# SmartSocket_Eth.net
KiCad netlist of a schematic drawn in EAGLE
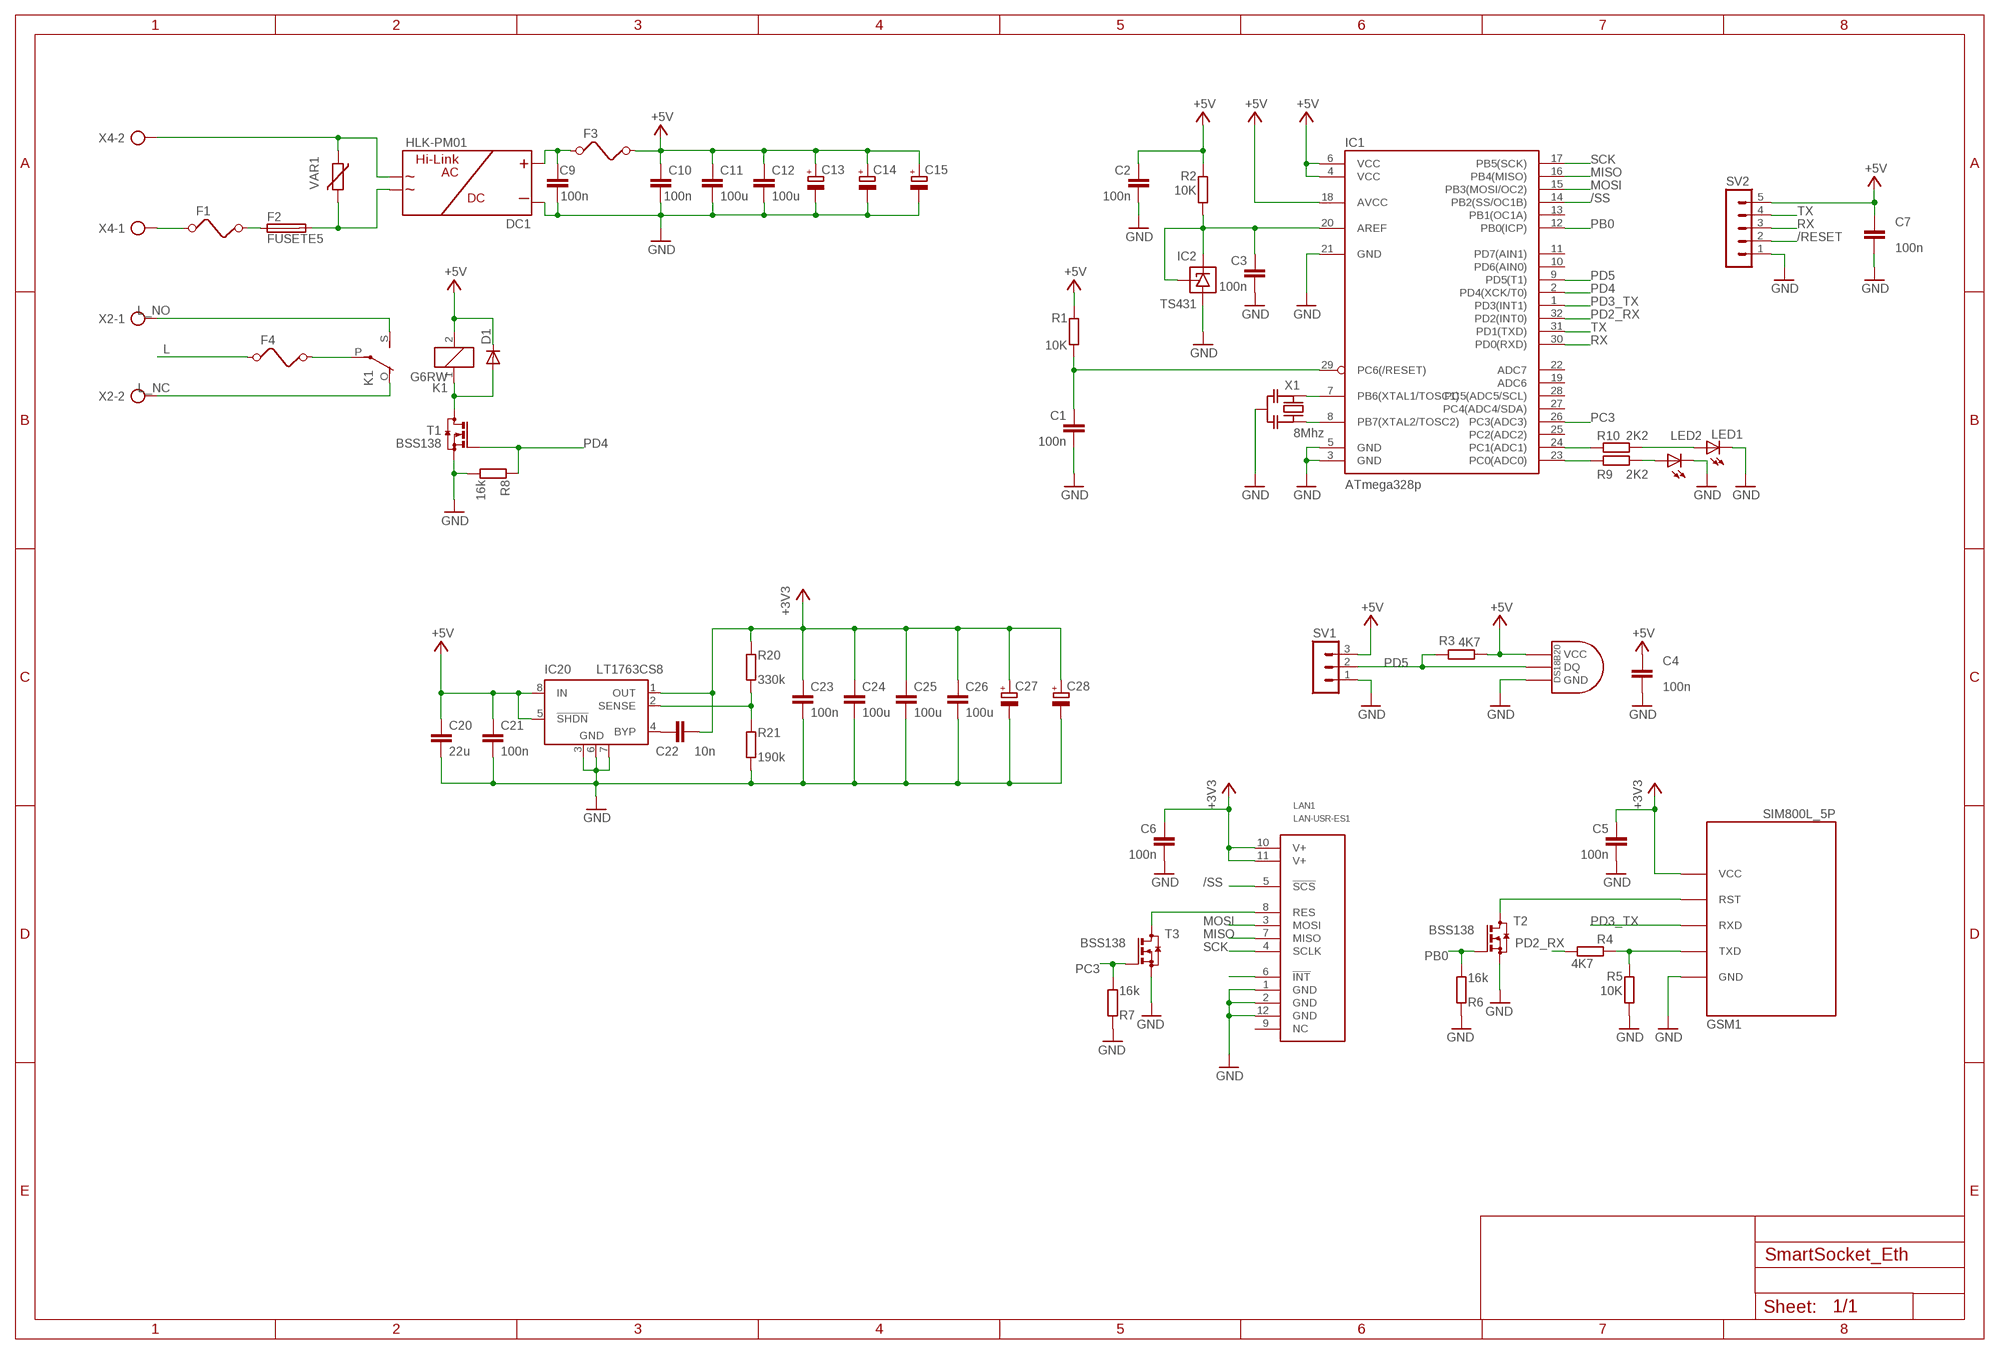
[diagram p0: schematic, sheet 1]

(export (version "E")
  (design (tool "Eeschema 10.0.6"))
  (components
    (comp (ref "18B20")
      (value "DS1820TO92")
      (footprint "eagle-import:DS1820")
      (libsource (lib "eagle-import") (part "DS1820TO92"))
    )
    (comp (ref "C1")
      (value "100n")
      (footprint "eagle-import:C0805")
      (libsource (lib "eagle-import") (part "C-EUC0805"))
    )
    (comp (ref "C2")
      (value "100n")
      (footprint "eagle-import:C0805")
      (libsource (lib "eagle-import") (part "C-EUC0805"))
    )
    (comp (ref "C3")
      (value "100n")
      (footprint "eagle-import:C0805")
      (libsource (lib "eagle-import") (part "C-EUC0805"))
    )
    (comp (ref "C4")
      (value "100n")
      (footprint "eagle-import:C0805")
      (libsource (lib "eagle-import") (part "C-EUC0805"))
    )
    (comp (ref "C5")
      (value "100n")
      (footprint "eagle-import:C0805")
      (libsource (lib "eagle-import") (part "C-EUC0805"))
    )
    (comp (ref "C6")
      (value "100n")
      (footprint "eagle-import:C0805")
      (libsource (lib "eagle-import") (part "C-EUC0805"))
    )
    (comp (ref "C7")
      (value "100n")
      (footprint "eagle-import:C0805")
      (libsource (lib "eagle-import") (part "C-EUC0805"))
    )
    (comp (ref "C9")
      (value "100n")
      (footprint "eagle-import:C0805")
      (libsource (lib "eagle-import") (part "C-EUC0805"))
    )
    (comp (ref "C10")
      (value "100n")
      (footprint "eagle-import:C0805")
      (libsource (lib "eagle-import") (part "C-EUC0805"))
    )
    (comp (ref "C11")
      (value "100u")
      (footprint "eagle-import:C1206")
      (libsource (lib "eagle-import") (part "C-EUC1206"))
    )
    (comp (ref "C12")
      (value "100u")
      (footprint "eagle-import:C1206")
      (libsource (lib "eagle-import") (part "C-EUC1206"))
    )
    (comp (ref "C13")
      (value "CPOL-EUE5-6")
      (footprint "eagle-import:E5-6")
      (libsource (lib "eagle-import") (part "CPOL-EUE5-6"))
    )
    (comp (ref "C14")
      (value "CPOL-EUSMCD")
      (footprint "eagle-import:SMC_D")
      (libsource (lib "eagle-import") (part "CPOL-EUSMCD"))
    )
    (comp (ref "C15")
      (value "CPOL-EUSMCD")
      (footprint "eagle-import:SMC_D")
      (libsource (lib "eagle-import") (part "CPOL-EUSMCD"))
    )
    (comp (ref "C20")
      (value "22u")
      (footprint "eagle-import:C0805")
      (libsource (lib "eagle-import") (part "C-EUC0805"))
    )
    (comp (ref "C21")
      (value "100n")
      (footprint "eagle-import:C0805")
      (libsource (lib "eagle-import") (part "C-EUC0805"))
    )
    (comp (ref "C22")
      (value "10n")
      (footprint "eagle-import:C0805")
      (libsource (lib "eagle-import") (part "C-EUC0805"))
    )
    (comp (ref "C23")
      (value "100n")
      (footprint "eagle-import:C1206")
      (libsource (lib "eagle-import") (part "C-EUC1206"))
    )
    (comp (ref "C24")
      (value "100u")
      (footprint "eagle-import:C1206")
      (libsource (lib "eagle-import") (part "C-EUC1206"))
    )
    (comp (ref "C25")
      (value "100u")
      (footprint "eagle-import:C1206")
      (libsource (lib "eagle-import") (part "C-EUC1206"))
    )
    (comp (ref "C26")
      (value "100u")
      (footprint "eagle-import:C1206")
      (libsource (lib "eagle-import") (part "C-EUC1206"))
    )
    (comp (ref "C27")
      (value "CPOL-EUE5-4")
      (footprint "eagle-import:E5-4")
      (libsource (lib "eagle-import") (part "CPOL-EUE5-4"))
    )
    (comp (ref "C28")
      (value "CPOL-EUSMCD")
      (footprint "eagle-import:SMC_D")
      (libsource (lib "eagle-import") (part "CPOL-EUSMCD"))
    )
    (comp (ref "D1")
      (value "DIODE-MELF-MLL41")
      (footprint "eagle-import:MELF-MLL41")
      (libsource (lib "eagle-import") (part "DIODE-MELF-MLL41"))
    )
    (comp (ref "DC1")
      (value "HLK-PM01")
      (footprint "eagle-import:HLK-3W")
      (libsource (lib "eagle-import") (part "HLK-PM01"))
    )
    (comp (ref "F1")
      (value "FUSE")
      (footprint "eagle-import:FUSE")
      (libsource (lib "eagle-import") (part "FUSE"))
    )
    (comp (ref "F2")
      (value "FUSETE5")
      (footprint "eagle-import:TE5")
      (libsource (lib "eagle-import") (part "FUSETE5"))
    )
    (comp (ref "F3")
      (value "FUSE")
      (footprint "eagle-import:FUSE")
      (libsource (lib "eagle-import") (part "FUSE"))
    )
    (comp (ref "F4")
      (value "FUSE")
      (footprint "eagle-import:FUSE")
      (libsource (lib "eagle-import") (part "FUSE"))
    )
    (comp (ref "GSM1")
      (value "SIM800L_5P")
      (footprint "eagle-import:SIM800L_5P")
      (libsource (lib "eagle-import") (part "SIM800L_5P"))
    )
    (comp (ref "IC1")
      (value "ATmega328p")
      (footprint "eagle-import:TQFP32-08")
      (fields (field (name "MPN") "ATMEGA8-16AU"))
      (libsource (lib "eagle-import") (part "MEGA8-AI"))
    )
    (comp (ref "IC2")
      (value "TS431")
      (footprint "eagle-import:SOT23")
      (libsource (lib "eagle-import") (part "TS431CX"))
    )
    (comp (ref "IC20")
      (value "LT1763CS8")
      (footprint "eagle-import:SOIC8")
      (fields (field (name "MPN") "LT1763CS8-2.5"))
      (libsource (lib "eagle-import") (part "LT1763CS8-2.5"))
    )
    (comp (ref "K1")
      (value "G6RW")
      (footprint "eagle-import:G6RW")
      (libsource (lib "eagle-import") (part "G6RW"))
    )
    (comp (ref "LAN1")
      (value "LAN-USR-ES1")
      (footprint "eagle-import:USR-ES1")
      (libsource (lib "eagle-import") (part "LAN-USR-ES1"))
    )
    (comp (ref "LED1")
      (value "LED3MM")
      (footprint "eagle-import:LED3MM")
      (libsource (lib "eagle-import") (part "LED3MM"))
    )
    (comp (ref "LED2")
      (value "LED3MM")
      (footprint "eagle-import:LED3MM")
      (libsource (lib "eagle-import") (part "LED3MM"))
    )
    (comp (ref "R1")
      (value "10K")
      (footprint "eagle-import:M0805")
      (libsource (lib "eagle-import") (part "R-EU_M0805"))
    )
    (comp (ref "R2")
      (value "10K")
      (footprint "eagle-import:M0805")
      (libsource (lib "eagle-import") (part "R-EU_M0805"))
    )
    (comp (ref "R3")
      (value "4K7")
      (footprint "eagle-import:M0805")
      (libsource (lib "eagle-import") (part "R-EU_M0805"))
    )
    (comp (ref "R4")
      (value "4K7")
      (footprint "eagle-import:M0805")
      (libsource (lib "eagle-import") (part "R-EU_M0805"))
    )
    (comp (ref "R5")
      (value "10K")
      (footprint "eagle-import:M0805")
      (libsource (lib "eagle-import") (part "R-EU_M0805"))
    )
    (comp (ref "R6")
      (value "16k")
      (footprint "eagle-import:M0805")
      (libsource (lib "eagle-import") (part "R-EU_M0805"))
    )
    (comp (ref "R7")
      (value "16k")
      (footprint "eagle-import:M0805")
      (libsource (lib "eagle-import") (part "R-EU_M0805"))
    )
    (comp (ref "R8")
      (value "16k")
      (footprint "eagle-import:M0805")
      (libsource (lib "eagle-import") (part "R-EU_M0805"))
    )
    (comp (ref "R9")
      (value "2K2")
      (footprint "eagle-import:M0805")
      (libsource (lib "eagle-import") (part "R-EU_M0805"))
    )
    (comp (ref "R10")
      (value "2K2")
      (footprint "eagle-import:M0805")
      (libsource (lib "eagle-import") (part "R-EU_M0805"))
    )
    (comp (ref "R20")
      (value "330k")
      (footprint "eagle-import:M0805")
      (libsource (lib "eagle-import") (part "R-EU_M0805"))
    )
    (comp (ref "R21")
      (value "190k")
      (footprint "eagle-import:M0805")
      (libsource (lib "eagle-import") (part "R-EU_M0805"))
    )
    (comp (ref "SV1")
      (value "MA03-1")
      (footprint "eagle-import:MA03-1")
      (libsource (lib "eagle-import") (part "MA03-1"))
    )
    (comp (ref "SV2")
      (value "MA05-1")
      (footprint "eagle-import:MA05-1")
      (libsource (lib "eagle-import") (part "MA05-1"))
    )
    (comp (ref "T1")
      (value "BSS138")
      (footprint "eagle-import:SOT23")
      (libsource (lib "eagle-import") (part "BSS123"))
    )
    (comp (ref "T2")
      (value "BSS138")
      (footprint "eagle-import:SOT23")
      (libsource (lib "eagle-import") (part "BSS123"))
    )
    (comp (ref "T3")
      (value "BSS138")
      (footprint "eagle-import:SOT23")
      (libsource (lib "eagle-import") (part "BSS123"))
    )
    (comp (ref "VAR1")
      (value "VARISTORS07K40")
      (footprint "eagle-import:S07K40")
      (libsource (lib "eagle-import") (part "VARISTORS07K40"))
    )
    (comp (ref "X1")
      (value "8Mhz")
      (footprint "eagle-import:CERALOCK_CSTCE_G")
      (libsource (lib "eagle-import") (part "CERMOSC-?CERALOCK-CSTCE_G"))
    )
    (comp (ref "X2")
      (value "AK500/2")
      (footprint "eagle-import:AK500_2")
      (libsource (lib "eagle-import") (part "AK500/2"))
    )
    (comp (ref "X4")
      (value "AK500/2")
      (footprint "eagle-import:AK500_2")
      (libsource (lib "eagle-import") (part "AK500/2"))
    )
  )
  (nets
    (net (code "1") (name "+3V3") (class "Default")
      (node (ref "C22") (pin "1") (pinfunction "1_1") (pintype "passive"))
      (node (ref "C23") (pin "1") (pinfunction "1_1") (pintype "passive"))
      (node (ref "C24") (pin "1") (pinfunction "1_1") (pintype "passive"))
      (node (ref "C25") (pin "1") (pinfunction "1_1") (pintype "passive"))
      (node (ref "C26") (pin "1") (pinfunction "1_1") (pintype "passive"))
      (node (ref "C27") (pin "+") (pinfunction "+_+") (pintype "passive"))
      (node (ref "C28") (pin "+") (pinfunction "+_+") (pintype "passive"))
      (node (ref "C5") (pin "2") (pinfunction "2_2") (pintype "passive"))
      (node (ref "C6") (pin "2") (pinfunction "2_2") (pintype "passive"))
      (node (ref "GSM1") (pin "P$1") (pinfunction "VCC_P$1") (pintype "bidirectional"))
      (node (ref "IC20") (pin "1") (pinfunction "OUT_1") (pintype "passive"))
      (node (ref "LAN1") (pin "10") (pinfunction "V+_10") (pintype "power_in"))
      (node (ref "LAN1") (pin "11") (pinfunction "V+_11") (pintype "power_in"))
      (node (ref "R20") (pin "2") (pinfunction "2_2") (pintype "passive"))
    )
    (net (code "2") (name "+5V") (class "Default")
      (node (ref "18B20") (pin "VDD") (pinfunction "VCC_VDD") (pintype "power_in"))
      (node (ref "C10") (pin "2") (pinfunction "2_2") (pintype "passive"))
      (node (ref "C11") (pin "1") (pinfunction "1_1") (pintype "passive"))
      (node (ref "C12") (pin "1") (pinfunction "1_1") (pintype "passive"))
      (node (ref "C13") (pin "+") (pinfunction "+_+") (pintype "passive"))
      (node (ref "C14") (pin "+") (pinfunction "+_+") (pintype "passive"))
      (node (ref "C15") (pin "+") (pinfunction "+_+") (pintype "passive"))
      (node (ref "C2") (pin "2") (pinfunction "2_2") (pintype "passive"))
      (node (ref "C20") (pin "1") (pinfunction "1_1") (pintype "passive"))
      (node (ref "C21") (pin "1") (pinfunction "1_1") (pintype "passive"))
      (node (ref "C4") (pin "2") (pinfunction "2_2") (pintype "passive"))
      (node (ref "C7") (pin "2") (pinfunction "2_2") (pintype "passive"))
      (node (ref "D1") (pin "C") (pinfunction "C_C") (pintype "passive"))
      (node (ref "F3") (pin "2") (pinfunction "2_2") (pintype "passive"))
      (node (ref "IC1") (pin "18") (pinfunction "AVCC_18") (pintype "power_in"))
      (node (ref "IC1") (pin "4") (pinfunction "VCC_4") (pintype "power_in"))
      (node (ref "IC1") (pin "6") (pinfunction "VCC_6") (pintype "power_in"))
      (node (ref "IC20") (pin "5") (pinfunction "~{SHDN}_5") (pintype "input"))
      (node (ref "IC20") (pin "8") (pinfunction "IN_8") (pintype "input"))
      (node (ref "K1") (pin "2") (pinfunction "2_2") (pintype "passive"))
      (node (ref "R1") (pin "2") (pinfunction "2_2") (pintype "passive"))
      (node (ref "R2") (pin "2") (pinfunction "2_2") (pintype "passive"))
      (node (ref "R3") (pin "2") (pinfunction "2_2") (pintype "passive"))
      (node (ref "SV1") (pin "3") (pinfunction "3_3") (pintype "passive"))
      (node (ref "SV2") (pin "5") (pinfunction "5_5") (pintype "passive"))
    )
    (net (code "3") (name "/L") (class "Default")
      (node (ref "F1") (pin "1") (pinfunction "1_1") (pintype "passive"))
      (node (ref "F4") (pin "1") (pinfunction "1_1") (pintype "passive"))
      (node (ref "X4") (pin "1") (pinfunction "KL_1") (pintype "passive"))
    )
    (net (code "4") (name "/L_NC") (class "Default")
      (node (ref "K1") (pin "O") (pinfunction "O_O") (pintype "passive"))
      (node (ref "X2") (pin "2") (pinfunction "KL_2") (pintype "passive"))
    )
    (net (code "5") (name "/L_NO") (class "Default")
      (node (ref "K1") (pin "S") (pinfunction "S_S") (pintype "passive"))
      (node (ref "X2") (pin "1") (pinfunction "KL_1") (pintype "passive"))
    )
    (net (code "6") (name "/MISO") (class "Default")
      (node (ref "IC1") (pin "16") (pinfunction "PB4(MISO)_16") (pintype "bidirectional"))
      (node (ref "LAN1") (pin "7") (pinfunction "MISO_7") (pintype "bidirectional"))
    )
    (net (code "7") (name "/MOSI") (class "Default")
      (node (ref "IC1") (pin "15") (pinfunction "PB3(MOSI/OC2)_15") (pintype "bidirectional"))
      (node (ref "LAN1") (pin "3") (pinfunction "MOSI_3") (pintype "bidirectional"))
    )
    (net (code "8") (name "/PB0") (class "Default")
      (node (ref "IC1") (pin "12") (pinfunction "PB0(ICP)_12") (pintype "bidirectional"))
      (node (ref "R6") (pin "2") (pinfunction "2_2") (pintype "passive"))
      (node (ref "T2") (pin "1") (pinfunction "G_1") (pintype "passive"))
    )
    (net (code "9") (name "/PC3") (class "Default")
      (node (ref "IC1") (pin "26") (pinfunction "PC3(ADC3)_26") (pintype "bidirectional"))
      (node (ref "R7") (pin "2") (pinfunction "2_2") (pintype "passive"))
      (node (ref "T3") (pin "1") (pinfunction "G_1") (pintype "passive"))
    )
    (net (code "10") (name "/PD2_RX") (class "Default")
      (node (ref "IC1") (pin "32") (pinfunction "PD2(INT0)_32") (pintype "bidirectional"))
      (node (ref "R4") (pin "2") (pinfunction "2_2") (pintype "passive"))
    )
    (net (code "11") (name "/PD3_TX") (class "Default")
      (node (ref "GSM1") (pin "P$3") (pinfunction "RXD_P$3") (pintype "bidirectional"))
      (node (ref "IC1") (pin "1") (pinfunction "PD3(INT1)_1") (pintype "bidirectional"))
    )
    (net (code "12") (name "/PD4") (class "Default")
      (node (ref "IC1") (pin "2") (pinfunction "PD4(XCK/T0)_2") (pintype "bidirectional"))
      (node (ref "R8") (pin "1") (pinfunction "1_1") (pintype "passive"))
      (node (ref "T1") (pin "1") (pinfunction "G_1") (pintype "passive"))
    )
    (net (code "13") (name "/PD5") (class "Default")
      (node (ref "18B20") (pin "DQ") (pinfunction "DQ_DQ") (pintype "bidirectional"))
      (node (ref "IC1") (pin "9") (pinfunction "PD5(T1)_9") (pintype "bidirectional"))
      (node (ref "R3") (pin "1") (pinfunction "1_1") (pintype "passive"))
      (node (ref "SV1") (pin "2") (pinfunction "2_2") (pintype "passive"))
    )
    (net (code "14") (name "/RX") (class "Default")
      (node (ref "IC1") (pin "30") (pinfunction "PD0(RXD)_30") (pintype "bidirectional"))
      (node (ref "SV2") (pin "3") (pinfunction "3_3") (pintype "passive"))
    )
    (net (code "15") (name "/SCK") (class "Default")
      (node (ref "IC1") (pin "17") (pinfunction "PB5(SCK)_17") (pintype "bidirectional"))
      (node (ref "LAN1") (pin "4") (pinfunction "SCLK_4") (pintype "input"))
    )
    (net (code "16") (name "/TX") (class "Default")
      (node (ref "IC1") (pin "31") (pinfunction "PD1(TXD)_31") (pintype "bidirectional"))
      (node (ref "SV2") (pin "4") (pinfunction "4_4") (pintype "passive"))
    )
    (net (code "17") (name "/{slash}RESET") (class "Default")
      (node (ref "C1") (pin "2") (pinfunction "2_2") (pintype "passive"))
      (node (ref "IC1") (pin "29") (pinfunction "PC6(/RESET)_29") (pintype "bidirectional"))
      (node (ref "R1") (pin "1") (pinfunction "1_1") (pintype "passive"))
      (node (ref "SV2") (pin "2") (pinfunction "2_2") (pintype "passive"))
    )
    (net (code "18") (name "/{slash}SS") (class "Default")
      (node (ref "IC1") (pin "14") (pinfunction "PB2(SS/OC1B)_14") (pintype "bidirectional"))
      (node (ref "LAN1") (pin "5") (pinfunction "~{SCS}_5") (pintype "input"))
    )
    (net (code "19") (name "GND") (class "Default")
      (node (ref "18B20") (pin "GND") (pinfunction "GND_GND") (pintype "power_in"))
      (node (ref "C1") (pin "1") (pinfunction "1_1") (pintype "passive"))
      (node (ref "C10") (pin "1") (pinfunction "1_1") (pintype "passive"))
      (node (ref "C11") (pin "2") (pinfunction "2_2") (pintype "passive"))
      (node (ref "C12") (pin "2") (pinfunction "2_2") (pintype "passive"))
      (node (ref "C13") (pin "-") (pinfunction "-_-") (pintype "passive"))
      (node (ref "C14") (pin "-") (pinfunction "-_-") (pintype "passive"))
      (node (ref "C15") (pin "-") (pinfunction "-_-") (pintype "passive"))
      (node (ref "C2") (pin "1") (pinfunction "1_1") (pintype "passive"))
      (node (ref "C20") (pin "2") (pinfunction "2_2") (pintype "passive"))
      (node (ref "C21") (pin "2") (pinfunction "2_2") (pintype "passive"))
      (node (ref "C23") (pin "2") (pinfunction "2_2") (pintype "passive"))
      (node (ref "C24") (pin "2") (pinfunction "2_2") (pintype "passive"))
      (node (ref "C25") (pin "2") (pinfunction "2_2") (pintype "passive"))
      (node (ref "C26") (pin "2") (pinfunction "2_2") (pintype "passive"))
      (node (ref "C27") (pin "-") (pinfunction "-_-") (pintype "passive"))
      (node (ref "C28") (pin "-") (pinfunction "-_-") (pintype "passive"))
      (node (ref "C3") (pin "1") (pinfunction "1_1") (pintype "passive"))
      (node (ref "C4") (pin "1") (pinfunction "1_1") (pintype "passive"))
      (node (ref "C5") (pin "1") (pinfunction "1_1") (pintype "passive"))
      (node (ref "C6") (pin "1") (pinfunction "1_1") (pintype "passive"))
      (node (ref "C7") (pin "1") (pinfunction "1_1") (pintype "passive"))
      (node (ref "C9") (pin "1") (pinfunction "1_1") (pintype "passive"))
      (node (ref "DC1") (pin "P$3") (pinfunction "P$3_P$3") (pintype "bidirectional"))
      (node (ref "GSM1") (pin "P$5") (pinfunction "GND_P$5") (pintype "bidirectional"))
      (node (ref "IC1") (pin "21") (pinfunction "GND_21") (pintype "power_in"))
      (node (ref "IC1") (pin "3") (pinfunction "GND_3") (pintype "power_in"))
      (node (ref "IC1") (pin "5") (pinfunction "GND_5") (pintype "power_in"))
      (node (ref "IC2") (pin "3") (pinfunction "A_3") (pintype "passive"))
      (node (ref "IC20") (pin "3") (pinfunction "GND_3") (pintype "power_in"))
      (node (ref "IC20") (pin "6") (pinfunction "GND_6") (pintype "power_in"))
      (node (ref "IC20") (pin "7") (pinfunction "GND_7") (pintype "power_in"))
      (node (ref "LAN1") (pin "1") (pinfunction "GND_1") (pintype "power_in"))
      (node (ref "LAN1") (pin "12") (pinfunction "GND_12") (pintype "power_in"))
      (node (ref "LAN1") (pin "2") (pinfunction "GND_2") (pintype "power_in"))
      (node (ref "LED1") (pin "K") (pinfunction "C_K") (pintype "passive"))
      (node (ref "LED2") (pin "K") (pinfunction "C_K") (pintype "passive"))
      (node (ref "R21") (pin "1") (pinfunction "1_1") (pintype "passive"))
      (node (ref "R5") (pin "1") (pinfunction "1_1") (pintype "passive"))
      (node (ref "R6") (pin "1") (pinfunction "1_1") (pintype "passive"))
      (node (ref "R7") (pin "1") (pinfunction "1_1") (pintype "passive"))
      (node (ref "R8") (pin "2") (pinfunction "2_2") (pintype "passive"))
      (node (ref "SV1") (pin "1") (pinfunction "1_1") (pintype "passive"))
      (node (ref "SV2") (pin "1") (pinfunction "1_1") (pintype "passive"))
      (node (ref "T1") (pin "2") (pinfunction "S_2") (pintype "passive"))
      (node (ref "T2") (pin "2") (pinfunction "S_2") (pintype "passive"))
      (node (ref "T3") (pin "2") (pinfunction "S_2") (pintype "passive"))
      (node (ref "X1") (pin "P$2") (pinfunction "GND_P$2") (pintype "passive"))
    )
    (net (code "20") (name "Net-(C9-Pad2)") (class "Default")
      (node (ref "C9") (pin "2") (pinfunction "2_2") (pintype "passive"))
      (node (ref "DC1") (pin "P$4") (pinfunction "P$4_P$4") (pintype "bidirectional"))
      (node (ref "F3") (pin "1") (pinfunction "1_1") (pintype "passive"))
    )
    (net (code "21") (name "Net-(DC1-PadP$2)") (class "Default")
      (node (ref "DC1") (pin "P$2") (pinfunction "P$2_P$2") (pintype "bidirectional"))
      (node (ref "F2") (pin "2") (pinfunction "2_2") (pintype "passive"))
      (node (ref "VAR1") (pin "2") (pinfunction "2_2") (pintype "passive"))
    )
    (net (code "22") (name "Net-(F1-Pad2)") (class "Default")
      (node (ref "F1") (pin "2") (pinfunction "2_2") (pintype "passive"))
      (node (ref "F2") (pin "1") (pinfunction "1_1") (pintype "passive"))
    )
    (net (code "23") (name "Net-(F4-Pad2)") (class "Default")
      (node (ref "F4") (pin "2") (pinfunction "2_2") (pintype "passive"))
      (node (ref "K1") (pin "P") (pinfunction "P_P") (pintype "passive"))
    )
    (net (code "24") (name "Net-(GSM1-RST)") (class "Default")
      (node (ref "GSM1") (pin "P$2") (pinfunction "RST_P$2") (pintype "bidirectional"))
      (node (ref "T2") (pin "3") (pinfunction "D_3") (pintype "passive"))
    )
    (net (code "25") (name "Net-(GSM1-TXD)") (class "Default")
      (node (ref "GSM1") (pin "P$4") (pinfunction "TXD_P$4") (pintype "bidirectional"))
      (node (ref "R4") (pin "1") (pinfunction "1_1") (pintype "passive"))
      (node (ref "R5") (pin "2") (pinfunction "2_2") (pintype "passive"))
    )
    (net (code "26") (name "Net-(IC1-AREF)") (class "Default")
      (node (ref "C3") (pin "2") (pinfunction "2_2") (pintype "passive"))
      (node (ref "IC1") (pin "20") (pinfunction "AREF_20") (pintype "passive"))
      (node (ref "IC2") (pin "1") (pinfunction "REF_1") (pintype "passive"))
      (node (ref "IC2") (pin "2") (pinfunction "C_2") (pintype "passive"))
      (node (ref "R2") (pin "1") (pinfunction "1_1") (pintype "passive"))
    )
    (net (code "27") (name "Net-(IC1-PB6(XTAL1{slash}TOSC1))") (class "Default")
      (node (ref "IC1") (pin "7") (pinfunction "PB6(XTAL1/TOSC1)_7") (pintype "bidirectional"))
      (node (ref "X1") (pin "P$3") (pinfunction "2_P$3") (pintype "passive"))
    )
    (net (code "28") (name "Net-(IC1-PB7(XTAL2{slash}TOSC2))") (class "Default")
      (node (ref "IC1") (pin "8") (pinfunction "PB7(XTAL2/TOSC2)_8") (pintype "bidirectional"))
      (node (ref "X1") (pin "P$1") (pinfunction "1_P$1") (pintype "passive"))
    )
    (net (code "29") (name "Net-(IC1-PC0(ADC0))") (class "Default")
      (node (ref "IC1") (pin "23") (pinfunction "PC0(ADC0)_23") (pintype "bidirectional"))
      (node (ref "R9") (pin "2") (pinfunction "2_2") (pintype "passive"))
    )
    (net (code "30") (name "Net-(IC1-PC1(ADC1))") (class "Default")
      (node (ref "IC1") (pin "24") (pinfunction "PC1(ADC1)_24") (pintype "bidirectional"))
      (node (ref "R10") (pin "2") (pinfunction "2_2") (pintype "passive"))
    )
    (net (code "31") (name "Net-(IC20-BYP)") (class "Default")
      (node (ref "C22") (pin "2") (pinfunction "2_2") (pintype "passive"))
      (node (ref "IC20") (pin "4") (pinfunction "BYP_4") (pintype "input"))
    )
    (net (code "32") (name "Net-(IC20-SENSE)") (class "Default")
      (node (ref "IC20") (pin "2") (pinfunction "SENSE_2") (pintype "input"))
      (node (ref "R20") (pin "1") (pinfunction "1_1") (pintype "passive"))
      (node (ref "R21") (pin "2") (pinfunction "2_2") (pintype "passive"))
    )
    (net (code "33") (name "Net-(LAN1-RES)") (class "Default")
      (node (ref "LAN1") (pin "8") (pinfunction "RES_8") (pintype "input"))
      (node (ref "T3") (pin "3") (pinfunction "D_3") (pintype "passive"))
    )
    (net (code "34") (name "Net-(LED1-PadA)") (class "Default")
      (node (ref "LED1") (pin "A") (pinfunction "A_A") (pintype "passive"))
      (node (ref "R10") (pin "1") (pinfunction "1_1") (pintype "passive"))
    )
    (net (code "35") (name "Net-(LED2-PadA)") (class "Default")
      (node (ref "LED2") (pin "A") (pinfunction "A_A") (pintype "passive"))
      (node (ref "R9") (pin "1") (pinfunction "1_1") (pintype "passive"))
    )
    (net (code "36") (name "Net-(T1-D)") (class "Default")
      (node (ref "D1") (pin "A") (pinfunction "A_A") (pintype "passive"))
      (node (ref "K1") (pin "1") (pinfunction "1_1") (pintype "passive"))
      (node (ref "T1") (pin "3") (pinfunction "D_3") (pintype "passive"))
    )
    (net (code "37") (name "Net-(X4B-KL)") (class "Default")
      (node (ref "DC1") (pin "P$1") (pinfunction "P$1_P$1") (pintype "bidirectional"))
      (node (ref "VAR1") (pin "1") (pinfunction "1_1") (pintype "passive"))
      (node (ref "X4") (pin "2") (pinfunction "KL_2") (pintype "passive"))
    )
    (net (code "38") (name "unconnected-(IC1-ADC6-Pad19)") (class "Default")
      (node (ref "IC1") (pin "19") (pinfunction "ADC6_19") (pintype "bidirectional"))
    )
    (net (code "39") (name "unconnected-(IC1-ADC7-Pad22)") (class "Default")
      (node (ref "IC1") (pin "22") (pinfunction "ADC7_22") (pintype "bidirectional"))
    )
    (net (code "40") (name "unconnected-(IC1-PB1(OC1A)-Pad13)") (class "Default")
      (node (ref "IC1") (pin "13") (pinfunction "PB1(OC1A)_13") (pintype "bidirectional"))
    )
    (net (code "41") (name "unconnected-(IC1-PC2(ADC2)-Pad25)") (class "Default")
      (node (ref "IC1") (pin "25") (pinfunction "PC2(ADC2)_25") (pintype "bidirectional"))
    )
    (net (code "42") (name "unconnected-(IC1-PC4(ADC4{slash}SDA)-Pad27)") (class "Default")
      (node (ref "IC1") (pin "27") (pinfunction "PC4(ADC4/SDA)_27") (pintype "bidirectional"))
    )
    (net (code "43") (name "unconnected-(IC1-PC5(ADC5{slash}SCL)-Pad28)") (class "Default")
      (node (ref "IC1") (pin "28") (pinfunction "PC5(ADC5/SCL)_28") (pintype "bidirectional"))
    )
    (net (code "44") (name "unconnected-(IC1-PD6(AIN0)-Pad10)") (class "Default")
      (node (ref "IC1") (pin "10") (pinfunction "PD6(AIN0)_10") (pintype "bidirectional"))
    )
    (net (code "45") (name "unconnected-(IC1-PD7(AIN1)-Pad11)") (class "Default")
      (node (ref "IC1") (pin "11") (pinfunction "PD7(AIN1)_11") (pintype "bidirectional"))
    )
    (net (code "46") (name "unconnected-(LAN1-NC-Pad9)") (class "Default")
      (node (ref "LAN1") (pin "9") (pinfunction "NC_9") (pintype "no_connect"))
    )
    (net (code "47") (name "unconnected-(LAN1-~{INT}-Pad6)") (class "Default")
      (node (ref "LAN1") (pin "6") (pinfunction "~{INT}_6") (pintype "output"))
    )
  )
)
